# rgbstripe_fft_lochraster.net
KiCad netlist of a schematic drawn in EAGLE
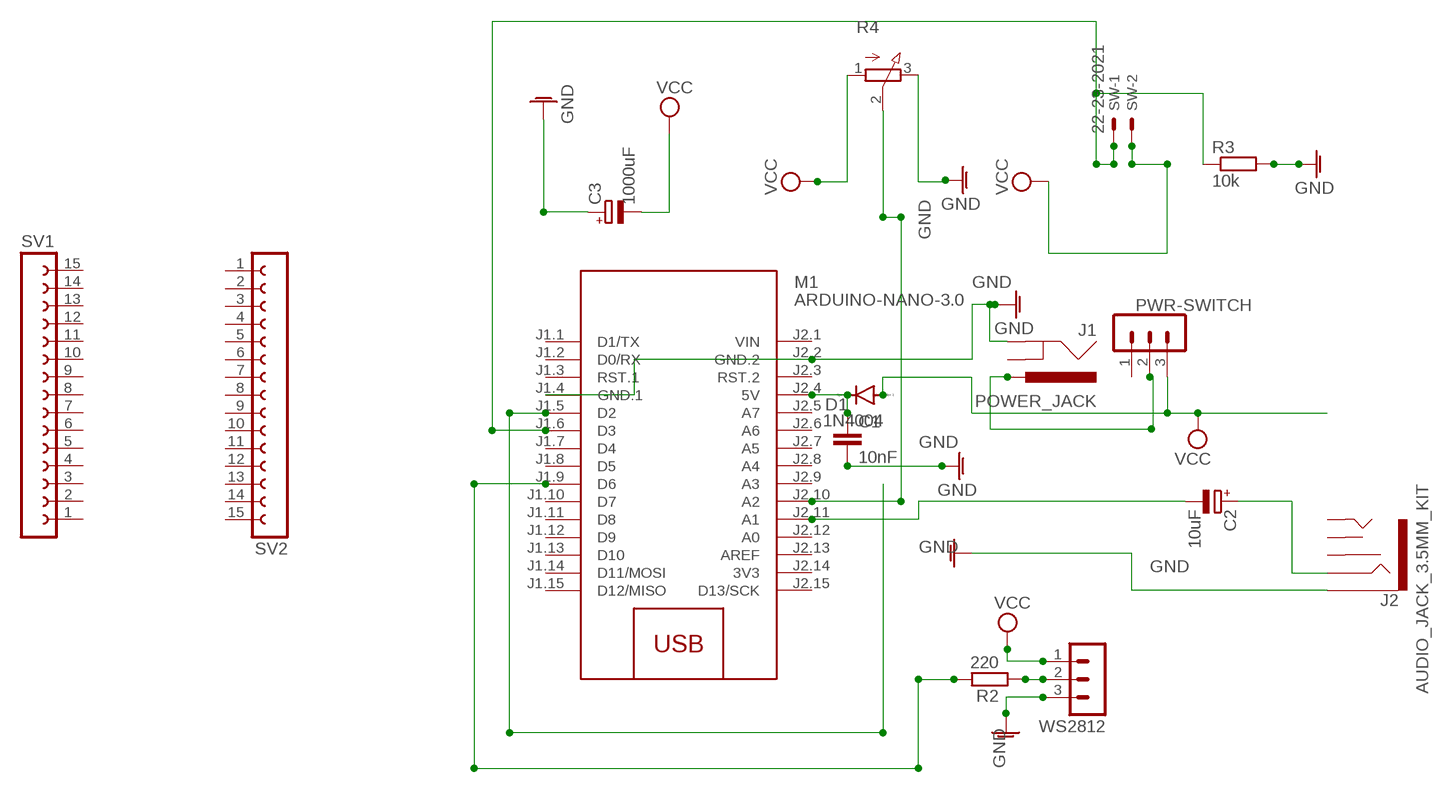
[diagram p0: schematic, sheet 1]

(export (version "E")
  (design (tool "Eeschema 10.0.6"))
  (components
    (comp (ref "C1")
      (value "10nF")
      (footprint "eagle-import:C025-025X050")
      (libsource (lib "eagle-import") (part "C-EU025-025X050"))
    )
    (comp (ref "C2")
      (value "10uF")
      (footprint "eagle-import:E2,5-6")
      (libsource (lib "eagle-import") (part "CPOL-EUE2.5-6"))
    )
    (comp (ref "C3")
      (value "1000uF")
      (footprint "eagle-import:E3,5-8")
      (libsource (lib "eagle-import") (part "CPOL-EUE3.5-8"))
    )
    (comp (ref "D1")
      (value "1N4004")
      (footprint "eagle-import:DO41-10")
      (libsource (lib "eagle-import") (part "1N4004"))
    )
    (comp (ref "J1")
      (value "POWER_JACK")
      (footprint "eagle-import:POWER_JACK_PTH")
      (libsource (lib "eagle-import") (part "POWER_JACK"))
    )
    (comp (ref "J2")
      (value "AUDIO_JACK_3.5MM_KIT")
      (footprint "eagle-import:AUDIO-JACK-KIT")
      (libsource (lib "eagle-import") (part "AUDIO_JACK_3.5MM_KIT"))
    )
    (comp (ref "M1")
      (value "ARDUINO-NANO-3.0")
      (footprint "eagle-import:ARDUINO-NANO-3.0")
      (libsource (lib "eagle-import") (part "ARDUINO-NANO-3.0"))
    )
    (comp (ref "PWR-SWITCH")
      (value "MA03-1")
      (footprint "eagle-import:MA03-1")
      (libsource (lib "eagle-import") (part "MA03-1"))
    )
    (comp (ref "R2")
      (value "220")
      (footprint "eagle-import:0204_5")
      (libsource (lib "eagle-import") (part "R-EU_0204/5"))
    )
    (comp (ref "R3")
      (value "10k")
      (footprint "eagle-import:0204_7")
      (libsource (lib "eagle-import") (part "R-EU_0204/7"))
    )
    (comp (ref "R4")
      (value "3RP/1610N")
      (footprint "eagle-import:3RP_1610N")
      (libsource (lib "eagle-import") (part "3RP/1610N"))
    )
    (comp (ref "SV1")
      (value "FE15-1")
      (footprint "eagle-import:FE15")
      (libsource (lib "eagle-import") (part "FE15-1"))
    )
    (comp (ref "SV2")
      (value "FE15-1")
      (footprint "eagle-import:FE15")
      (libsource (lib "eagle-import") (part "FE15-1"))
    )
    (comp (ref "SW")
      (value "22-23-2021")
      (footprint "eagle-import:22-23-2021")
      (fields (field (name "MF") "MOLEX"))
      (libsource (lib "eagle-import") (part "22-23-2021"))
    )
    (comp (ref "WS2812")
      (value "MA03-1")
      (footprint "eagle-import:MA03-1")
      (libsource (lib "eagle-import") (part "MA03-1"))
    )
  )
  (nets
    (net (code "1") (name "/3V3") (class "Default")
      (node (ref "M1") (pin "J2.14") (pinfunction "3V3_J2.14") (pintype "power_in"))
    )
    (net (code "2") (name "/VIN") (class "Default")
      (node (ref "M1") (pin "J2.1") (pinfunction "VIN_J2.1") (pintype "power_in"))
    )
    (net (code "3") (name "GND") (class "Default")
      (node (ref "C1") (pin "2") (pinfunction "2_2") (pintype "passive"))
      (node (ref "C3") (pin "+") (pinfunction "+_+") (pintype "passive"))
      (node (ref "J1") (pin "GND") (pinfunction "GND_GND") (pintype "bidirectional"))
      (node (ref "J2") (pin "SLEEVE") (pinfunction "SLEEVE_SLEEVE") (pintype "bidirectional"))
      (node (ref "M1") (pin "J1.4") (pinfunction "GND.1_J1.4") (pintype "power_in"))
      (node (ref "M1") (pin "J2.2") (pinfunction "GND.2_J2.2") (pintype "power_in"))
      (node (ref "R3") (pin "2") (pinfunction "2_2") (pintype "passive"))
      (node (ref "R4") (pin "3") (pinfunction "E_3") (pintype "passive"))
      (node (ref "WS2812") (pin "3") (pinfunction "3_3") (pintype "passive"))
    )
    (net (code "4") (name "Net-(C2-Pad+)") (class "Default")
      (node (ref "C2") (pin "+") (pinfunction "+_+") (pintype "passive"))
      (node (ref "J2") (pin "RING") (pinfunction "RING_RING") (pintype "bidirectional"))
    )
    (net (code "5") (name "Net-(J1-PadPWR)") (class "Default")
      (node (ref "J1") (pin "PWR") (pinfunction "PWR_PWR") (pintype "bidirectional"))
      (node (ref "PWR-SWITCH") (pin "2") (pinfunction "2_2") (pintype "passive"))
    )
    (net (code "6") (name "Net-(M1-5V)") (class "Default")
      (node (ref "C1") (pin "1") (pinfunction "1_1") (pintype "passive"))
      (node (ref "D1") (pin "C") (pinfunction "C_C") (pintype "passive"))
      (node (ref "M1") (pin "J2.4") (pinfunction "5V_J2.4") (pintype "power_in"))
    )
    (net (code "7") (name "Net-(M1-A1)") (class "Default")
      (node (ref "C2") (pin "-") (pinfunction "-_-") (pintype "passive"))
      (node (ref "M1") (pin "J2.11") (pinfunction "A1_J2.11") (pintype "bidirectional"))
    )
    (net (code "8") (name "Net-(M1-A2)") (class "Default")
      (node (ref "M1") (pin "J2.10") (pinfunction "A2_J2.10") (pintype "bidirectional"))
      (node (ref "R4") (pin "2") (pinfunction "S_2") (pintype "passive"))
    )
    (net (code "9") (name "Net-(M1-D3)") (class "Default")
      (node (ref "M1") (pin "J1.6") (pinfunction "D3_J1.6") (pintype "bidirectional"))
      (node (ref "R3") (pin "1") (pinfunction "1_1") (pintype "passive"))
      (node (ref "SW") (pin "1") (pinfunction "S_1") (pintype "passive"))
    )
    (net (code "10") (name "Net-(M1-D6)") (class "Default")
      (node (ref "M1") (pin "J1.9") (pinfunction "D6_J1.9") (pintype "bidirectional"))
      (node (ref "R2") (pin "2") (pinfunction "2_2") (pintype "passive"))
    )
    (net (code "11") (name "Net-(R2-Pad1)") (class "Default")
      (node (ref "R2") (pin "1") (pinfunction "1_1") (pintype "passive"))
      (node (ref "WS2812") (pin "2") (pinfunction "2_2") (pintype "passive"))
    )
    (net (code "12") (name "VCC") (class "Default")
      (node (ref "C3") (pin "-") (pinfunction "-_-") (pintype "passive"))
      (node (ref "D1") (pin "A") (pinfunction "A_A") (pintype "passive"))
      (node (ref "PWR-SWITCH") (pin "3") (pinfunction "3_3") (pintype "passive"))
      (node (ref "R4") (pin "1") (pinfunction "A_1") (pintype "passive"))
      (node (ref "SW") (pin "2") (pinfunction "S_2") (pintype "passive"))
      (node (ref "WS2812") (pin "1") (pinfunction "1_1") (pintype "passive"))
    )
    (net (code "13") (name "unconnected-(J1-PadGNDBREAK)") (class "Default")
      (node (ref "J1") (pin "GNDBREAK") (pinfunction "GNDBREAK_GNDBREAK") (pintype "bidirectional"))
    )
    (net (code "14") (name "unconnected-(J2-PadRSH)") (class "Default")
      (node (ref "J2") (pin "RSH") (pinfunction "RSH_RSH") (pintype "bidirectional"))
    )
    (net (code "15") (name "unconnected-(J2-PadTIP)") (class "Default")
      (node (ref "J2") (pin "TIP") (pinfunction "TIP_TIP") (pintype "bidirectional"))
    )
    (net (code "16") (name "unconnected-(J2-PadTSH)") (class "Default")
      (node (ref "J2") (pin "TSH") (pinfunction "TSH_TSH") (pintype "bidirectional"))
    )
    (net (code "17") (name "unconnected-(M1-A0-PadJ2.12)") (class "Default")
      (node (ref "M1") (pin "J2.12") (pinfunction "A0_J2.12") (pintype "bidirectional"))
    )
    (net (code "18") (name "unconnected-(M1-A3-PadJ2.9)") (class "Default")
      (node (ref "M1") (pin "J2.9") (pinfunction "A3_J2.9") (pintype "bidirectional"))
    )
    (net (code "19") (name "unconnected-(M1-A4-PadJ2.8)") (class "Default")
      (node (ref "M1") (pin "J2.8") (pinfunction "A4_J2.8") (pintype "bidirectional"))
    )
    (net (code "20") (name "unconnected-(M1-A5-PadJ2.7)") (class "Default")
      (node (ref "M1") (pin "J2.7") (pinfunction "A5_J2.7") (pintype "bidirectional"))
    )
    (net (code "21") (name "unconnected-(M1-A6-PadJ2.6)") (class "Default")
      (node (ref "M1") (pin "J2.6") (pinfunction "A6_J2.6") (pintype "bidirectional"))
    )
    (net (code "22") (name "unconnected-(M1-A7-PadJ2.5)") (class "Default")
      (node (ref "M1") (pin "J2.5") (pinfunction "A7_J2.5") (pintype "bidirectional"))
    )
    (net (code "23") (name "unconnected-(M1-AREF-PadJ2.13)") (class "Default")
      (node (ref "M1") (pin "J2.13") (pinfunction "AREF_J2.13") (pintype "bidirectional"))
    )
    (net (code "24") (name "unconnected-(M1-D0{slash}RX-PadJ1.2)") (class "Default")
      (node (ref "M1") (pin "J1.2") (pinfunction "D0/RX_J1.2") (pintype "bidirectional"))
    )
    (net (code "25") (name "unconnected-(M1-D1{slash}TX-PadJ1.1)") (class "Default")
      (node (ref "M1") (pin "J1.1") (pinfunction "D1/TX_J1.1") (pintype "bidirectional"))
    )
    (net (code "26") (name "unconnected-(M1-D2-PadJ1.5)") (class "Default")
      (node (ref "M1") (pin "J1.5") (pinfunction "D2_J1.5") (pintype "bidirectional"))
    )
    (net (code "27") (name "unconnected-(M1-D4-PadJ1.7)") (class "Default")
      (node (ref "M1") (pin "J1.7") (pinfunction "D4_J1.7") (pintype "bidirectional"))
    )
    (net (code "28") (name "unconnected-(M1-D5-PadJ1.8)") (class "Default")
      (node (ref "M1") (pin "J1.8") (pinfunction "D5_J1.8") (pintype "bidirectional"))
    )
    (net (code "29") (name "unconnected-(M1-D7-PadJ1.10)") (class "Default")
      (node (ref "M1") (pin "J1.10") (pinfunction "D7_J1.10") (pintype "bidirectional"))
    )
    (net (code "30") (name "unconnected-(M1-D8-PadJ1.11)") (class "Default")
      (node (ref "M1") (pin "J1.11") (pinfunction "D8_J1.11") (pintype "bidirectional"))
    )
    (net (code "31") (name "unconnected-(M1-D9-PadJ1.12)") (class "Default")
      (node (ref "M1") (pin "J1.12") (pinfunction "D9_J1.12") (pintype "bidirectional"))
    )
    (net (code "32") (name "unconnected-(M1-D10-PadJ1.13)") (class "Default")
      (node (ref "M1") (pin "J1.13") (pinfunction "D10_J1.13") (pintype "bidirectional"))
    )
    (net (code "33") (name "unconnected-(M1-D11{slash}MOSI-PadJ1.14)") (class "Default")
      (node (ref "M1") (pin "J1.14") (pinfunction "D11/MOSI_J1.14") (pintype "bidirectional"))
    )
    (net (code "34") (name "unconnected-(M1-D12{slash}MISO-PadJ1.15)") (class "Default")
      (node (ref "M1") (pin "J1.15") (pinfunction "D12/MISO_J1.15") (pintype "bidirectional"))
    )
    (net (code "35") (name "unconnected-(M1-D13{slash}SCK-PadJ2.15)") (class "Default")
      (node (ref "M1") (pin "J2.15") (pinfunction "D13/SCK_J2.15") (pintype "bidirectional"))
    )
    (net (code "36") (name "unconnected-(M1-RST.1-PadJ1.3)") (class "Default")
      (node (ref "M1") (pin "J1.3") (pinfunction "RST.1_J1.3") (pintype "bidirectional"))
    )
    (net (code "37") (name "unconnected-(M1-RST.2-PadJ2.3)") (class "Default")
      (node (ref "M1") (pin "J2.3") (pinfunction "RST.2_J2.3") (pintype "bidirectional"))
    )
    (net (code "38") (name "unconnected-(PWR-SWITCH-Pad1)") (class "Default")
      (node (ref "PWR-SWITCH") (pin "1") (pinfunction "1_1") (pintype "passive"))
    )
    (net (code "39") (name "unconnected-(SV1-Pad1)") (class "Default")
      (node (ref "SV1") (pin "1") (pinfunction "1_1") (pintype "passive"))
    )
    (net (code "40") (name "unconnected-(SV1-Pad2)") (class "Default")
      (node (ref "SV1") (pin "2") (pinfunction "2_2") (pintype "passive"))
    )
    (net (code "41") (name "unconnected-(SV1-Pad3)") (class "Default")
      (node (ref "SV1") (pin "3") (pinfunction "3_3") (pintype "passive"))
    )
    (net (code "42") (name "unconnected-(SV1-Pad4)") (class "Default")
      (node (ref "SV1") (pin "4") (pinfunction "4_4") (pintype "passive"))
    )
    (net (code "43") (name "unconnected-(SV1-Pad5)") (class "Default")
      (node (ref "SV1") (pin "5") (pinfunction "5_5") (pintype "passive"))
    )
    (net (code "44") (name "unconnected-(SV1-Pad6)") (class "Default")
      (node (ref "SV1") (pin "6") (pinfunction "6_6") (pintype "passive"))
    )
    (net (code "45") (name "unconnected-(SV1-Pad7)") (class "Default")
      (node (ref "SV1") (pin "7") (pinfunction "7_7") (pintype "passive"))
    )
    (net (code "46") (name "unconnected-(SV1-Pad8)") (class "Default")
      (node (ref "SV1") (pin "8") (pinfunction "8_8") (pintype "passive"))
    )
    (net (code "47") (name "unconnected-(SV1-Pad9)") (class "Default")
      (node (ref "SV1") (pin "9") (pinfunction "9_9") (pintype "passive"))
    )
    (net (code "48") (name "unconnected-(SV1-Pad10)") (class "Default")
      (node (ref "SV1") (pin "10") (pinfunction "10_10") (pintype "passive"))
    )
    (net (code "49") (name "unconnected-(SV1-Pad11)") (class "Default")
      (node (ref "SV1") (pin "11") (pinfunction "11_11") (pintype "passive"))
    )
    (net (code "50") (name "unconnected-(SV1-Pad12)") (class "Default")
      (node (ref "SV1") (pin "12") (pinfunction "12_12") (pintype "passive"))
    )
    (net (code "51") (name "unconnected-(SV1-Pad13)") (class "Default")
      (node (ref "SV1") (pin "13") (pinfunction "13_13") (pintype "passive"))
    )
    (net (code "52") (name "unconnected-(SV1-Pad14)") (class "Default")
      (node (ref "SV1") (pin "14") (pinfunction "14_14") (pintype "passive"))
    )
    (net (code "53") (name "unconnected-(SV1-Pad15)") (class "Default")
      (node (ref "SV1") (pin "15") (pinfunction "15_15") (pintype "passive"))
    )
    (net (code "54") (name "unconnected-(SV2-Pad1)") (class "Default")
      (node (ref "SV2") (pin "1") (pinfunction "1_1") (pintype "passive"))
    )
    (net (code "55") (name "unconnected-(SV2-Pad2)") (class "Default")
      (node (ref "SV2") (pin "2") (pinfunction "2_2") (pintype "passive"))
    )
    (net (code "56") (name "unconnected-(SV2-Pad3)") (class "Default")
      (node (ref "SV2") (pin "3") (pinfunction "3_3") (pintype "passive"))
    )
    (net (code "57") (name "unconnected-(SV2-Pad4)") (class "Default")
      (node (ref "SV2") (pin "4") (pinfunction "4_4") (pintype "passive"))
    )
    (net (code "58") (name "unconnected-(SV2-Pad5)") (class "Default")
      (node (ref "SV2") (pin "5") (pinfunction "5_5") (pintype "passive"))
    )
    (net (code "59") (name "unconnected-(SV2-Pad6)") (class "Default")
      (node (ref "SV2") (pin "6") (pinfunction "6_6") (pintype "passive"))
    )
    (net (code "60") (name "unconnected-(SV2-Pad7)") (class "Default")
      (node (ref "SV2") (pin "7") (pinfunction "7_7") (pintype "passive"))
    )
    (net (code "61") (name "unconnected-(SV2-Pad8)") (class "Default")
      (node (ref "SV2") (pin "8") (pinfunction "8_8") (pintype "passive"))
    )
    (net (code "62") (name "unconnected-(SV2-Pad9)") (class "Default")
      (node (ref "SV2") (pin "9") (pinfunction "9_9") (pintype "passive"))
    )
    (net (code "63") (name "unconnected-(SV2-Pad10)") (class "Default")
      (node (ref "SV2") (pin "10") (pinfunction "10_10") (pintype "passive"))
    )
    (net (code "64") (name "unconnected-(SV2-Pad11)") (class "Default")
      (node (ref "SV2") (pin "11") (pinfunction "11_11") (pintype "passive"))
    )
    (net (code "65") (name "unconnected-(SV2-Pad12)") (class "Default")
      (node (ref "SV2") (pin "12") (pinfunction "12_12") (pintype "passive"))
    )
    (net (code "66") (name "unconnected-(SV2-Pad13)") (class "Default")
      (node (ref "SV2") (pin "13") (pinfunction "13_13") (pintype "passive"))
    )
    (net (code "67") (name "unconnected-(SV2-Pad14)") (class "Default")
      (node (ref "SV2") (pin "14") (pinfunction "14_14") (pintype "passive"))
    )
    (net (code "68") (name "unconnected-(SV2-Pad15)") (class "Default")
      (node (ref "SV2") (pin "15") (pinfunction "15_15") (pintype "passive"))
    )
  )
)
